# ig-normal-ver12_rev.net
KiCad netlist of a schematic drawn in EAGLE
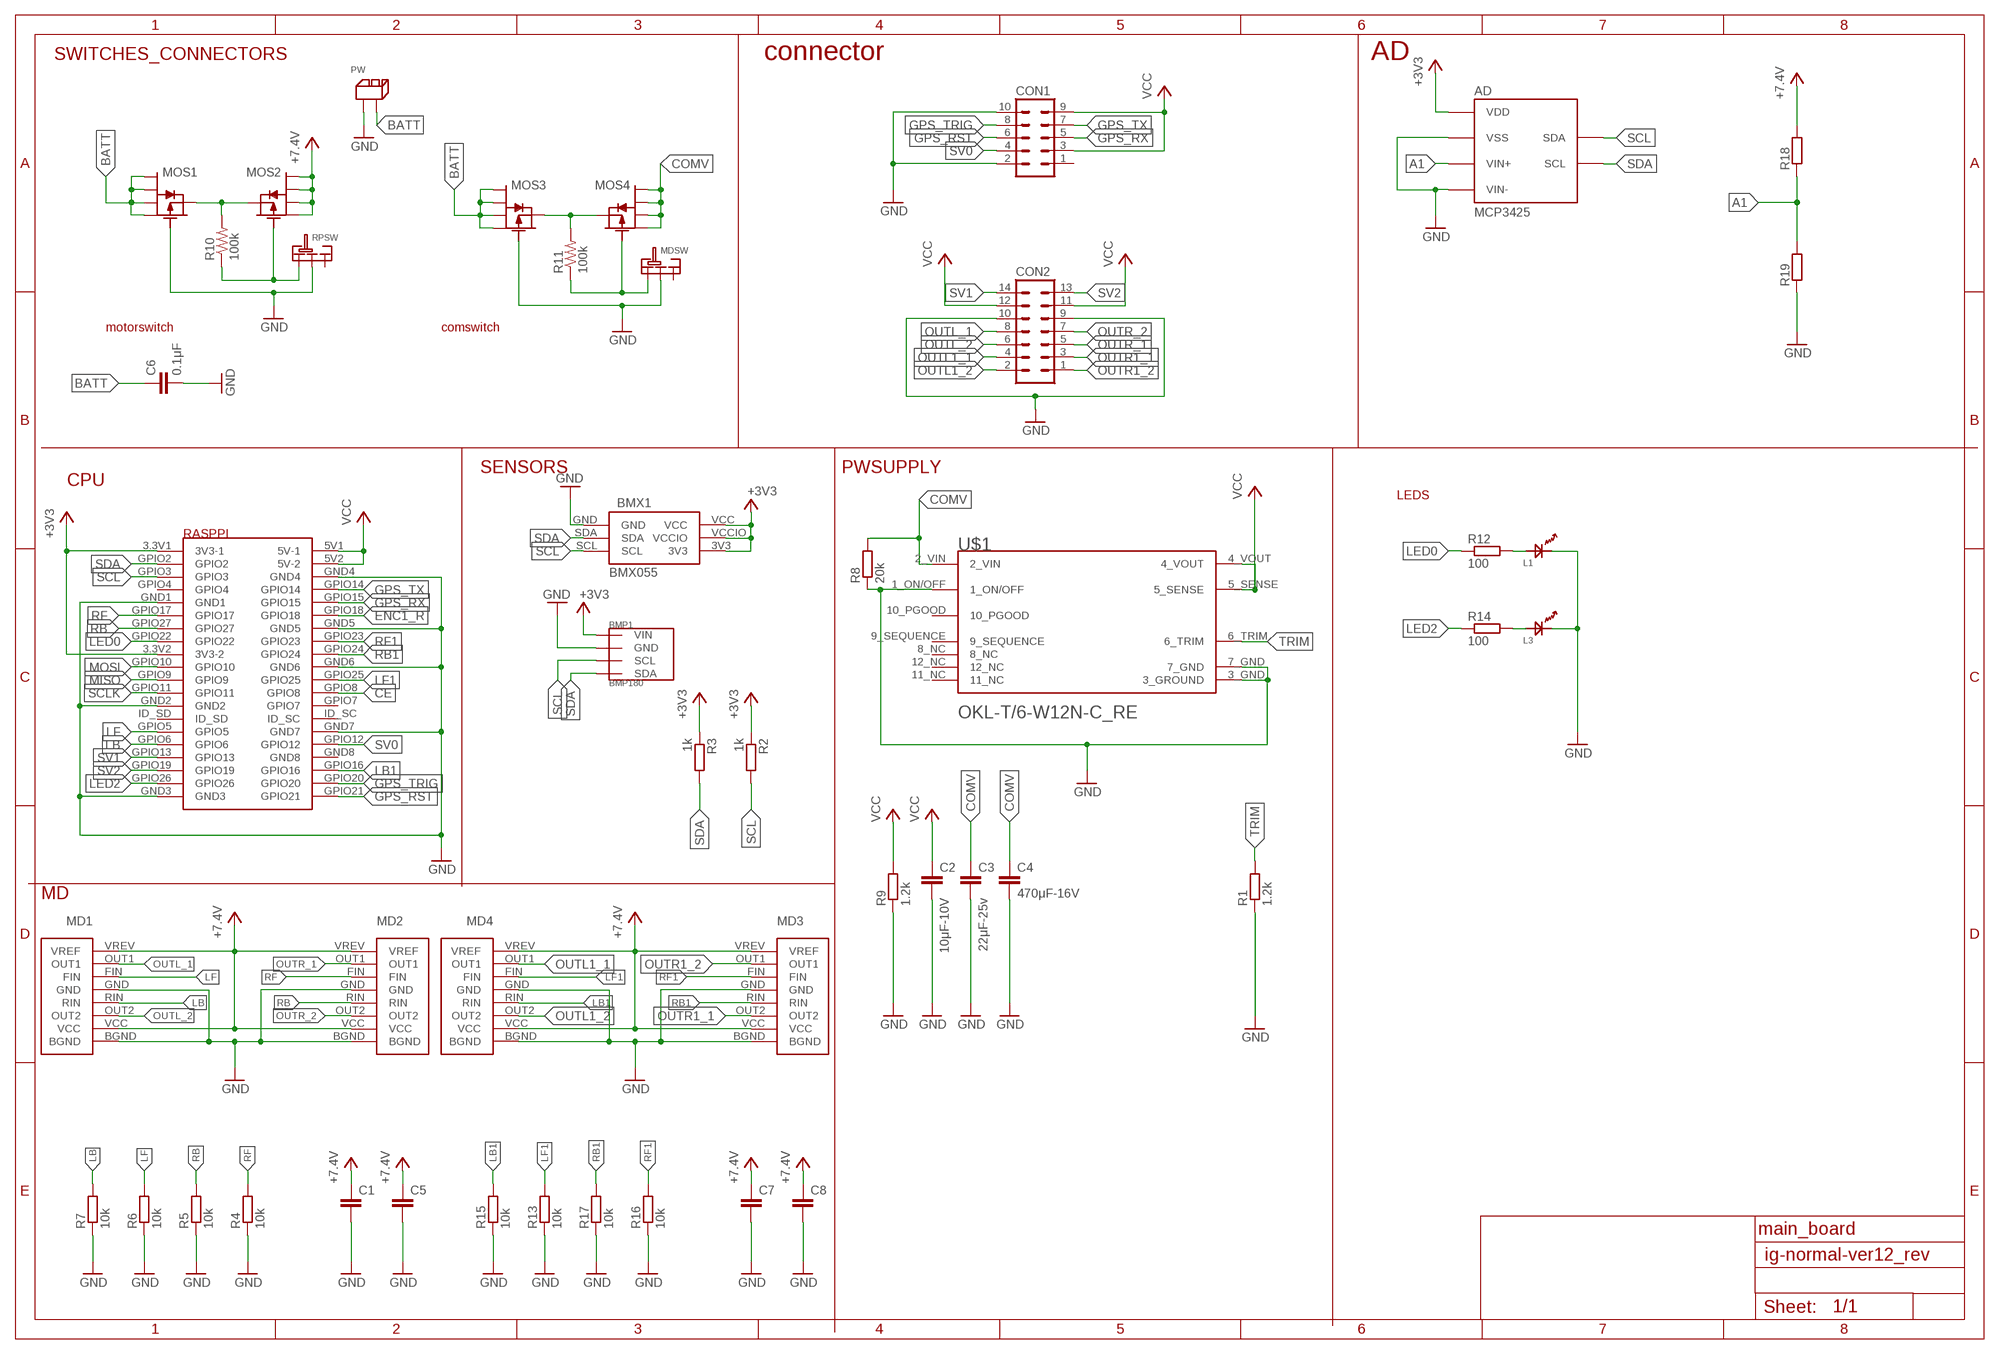
[diagram p0: schematic, sheet 1]

(export (version "E")
  (design (tool "Eeschema 10.0.6"))
  (components
    (comp (ref "AD")
      (value "MCP3425")
      (footprint "eagle-import:SOT23-6")
      (libsource (lib "eagle-import") (part "MCP3425"))
    )
    (comp (ref "BMP1")
      (value "BMP180")
      (footprint "eagle-import:GY-68")
      (libsource (lib "eagle-import") (part "BMP180"))
    )
    (comp (ref "BMX1")
      (value "BMX055")
      (footprint "eagle-import:BMX055")
      (libsource (lib "eagle-import") (part "BMX055"))
    )
    (comp (ref "C1")
      (value "C-EUC0603")
      (footprint "eagle-import:C0603")
      (libsource (lib "eagle-import") (part "C-EUC0603"))
    )
    (comp (ref "C2")
      (value "10μF-10V")
      (footprint "eagle-import:C0603")
      (libsource (lib "eagle-import") (part "C-EUC0603"))
    )
    (comp (ref "C3")
      (value "22μF-25v")
      (footprint "eagle-import:C0805")
      (libsource (lib "eagle-import") (part "C-EUC0805"))
    )
    (comp (ref "C4")
      (value "470μF-16V")
      (footprint "eagle-import:C0603")
      (libsource (lib "eagle-import") (part "C-EUC0603"))
    )
    (comp (ref "C5")
      (value "C-EUC0603")
      (footprint "eagle-import:C0603")
      (libsource (lib "eagle-import") (part "C-EUC0603"))
    )
    (comp (ref "C6")
      (value "0.1μF")
      (footprint "eagle-import:C0603")
      (libsource (lib "eagle-import") (part "C-EUC0603"))
    )
    (comp (ref "C7")
      (value "C-EUC0603")
      (footprint "eagle-import:C0603")
      (libsource (lib "eagle-import") (part "C-EUC0603"))
    )
    (comp (ref "C8")
      (value "C-EUC0603")
      (footprint "eagle-import:C0603")
      (libsource (lib "eagle-import") (part "C-EUC0603"))
    )
    (comp (ref "CON1")
      (value "ML10L")
      (footprint "eagle-import:ML10L")
      (libsource (lib "eagle-import") (part "ML10L"))
    )
    (comp (ref "CON2")
      (value "ML14L")
      (footprint "eagle-import:ML14L")
      (libsource (lib "eagle-import") (part "ML14L"))
    )
    (comp (ref "L1")
      (value "OSXX1608C1A")
      (footprint "eagle-import:OSXX1608C1A")
      (libsource (lib "eagle-import") (part "OSXX1608C1A"))
    )
    (comp (ref "L3")
      (value "OSXX1608C1A")
      (footprint "eagle-import:OSXX1608C1A")
      (libsource (lib "eagle-import") (part "OSXX1608C1A"))
    )
    (comp (ref "MD1")
      (value "BD6222HFP-TR")
      (footprint "eagle-import:BD6222HFP-TR")
      (libsource (lib "eagle-import") (part "BD6222HFP-TR"))
    )
    (comp (ref "MD2")
      (value "BD6222HFP-TR")
      (footprint "eagle-import:BD6222HFP-TR")
      (libsource (lib "eagle-import") (part "BD6222HFP-TR"))
    )
    (comp (ref "MD3")
      (value "BD6222HFP-TR")
      (footprint "eagle-import:BD6222HFP-TR")
      (libsource (lib "eagle-import") (part "BD6222HFP-TR"))
    )
    (comp (ref "MD4")
      (value "BD6222HFP-TR")
      (footprint "eagle-import:BD6222HFP-TR")
      (libsource (lib "eagle-import") (part "BD6222HFP-TR"))
    )
    (comp (ref "MDSW")
      (value "SRIDE_SWITCH")
      (footprint "eagle-import:SRIDE_SWITCH")
      (libsource (lib "eagle-import") (part "SRIDE_SWITCH"))
    )
    (comp (ref "MOS1")
      (value "PCH_SSM6J808R")
      (footprint "eagle-import:SSM6J808R")
      (libsource (lib "eagle-import") (part "PCH_SSM6J808R"))
    )
    (comp (ref "MOS2")
      (value "PCH_SSM6J808R")
      (footprint "eagle-import:SSM6J808R")
      (libsource (lib "eagle-import") (part "PCH_SSM6J808R"))
    )
    (comp (ref "MOS3")
      (value "PCH_SSM6J808R")
      (footprint "eagle-import:SSM6J808R")
      (libsource (lib "eagle-import") (part "PCH_SSM6J808R"))
    )
    (comp (ref "MOS4")
      (value "PCH_SSM6J808R")
      (footprint "eagle-import:SSM6J808R")
      (libsource (lib "eagle-import") (part "PCH_SSM6J808R"))
    )
    (comp (ref "PW")
      (value "2PIN")
      (footprint "eagle-import:2PIN")
      (libsource (lib "eagle-import") (part "2PIN"))
    )
    (comp (ref "R1")
      (value "1.2k")
      (footprint "eagle-import:R0805")
      (libsource (lib "eagle-import") (part "R-EU_R0805"))
    )
    (comp (ref "R2")
      (value "1k")
      (footprint "eagle-import:R0603")
      (libsource (lib "eagle-import") (part "R-EU_R0603"))
    )
    (comp (ref "R3")
      (value "1k")
      (footprint "eagle-import:R0603")
      (libsource (lib "eagle-import") (part "R-EU_R0603"))
    )
    (comp (ref "R4")
      (value "10k")
      (footprint "eagle-import:R0603")
      (libsource (lib "eagle-import") (part "R-EU_R0603"))
    )
    (comp (ref "R5")
      (value "10k")
      (footprint "eagle-import:R0603")
      (libsource (lib "eagle-import") (part "R-EU_R0603"))
    )
    (comp (ref "R6")
      (value "10k")
      (footprint "eagle-import:R0603")
      (libsource (lib "eagle-import") (part "R-EU_R0603"))
    )
    (comp (ref "R7")
      (value "10k")
      (footprint "eagle-import:R0603")
      (libsource (lib "eagle-import") (part "R-EU_R0603"))
    )
    (comp (ref "R8")
      (value "20k")
      (footprint "eagle-import:R0603")
      (libsource (lib "eagle-import") (part "R-EU_R0603"))
    )
    (comp (ref "R9")
      (value "1.2k")
      (footprint "eagle-import:R0805")
      (libsource (lib "eagle-import") (part "R-EU_R0805"))
    )
    (comp (ref "R10")
      (value "100k")
      (footprint "eagle-import:R0603")
      (libsource (lib "eagle-import") (part "R-US_R0603"))
    )
    (comp (ref "R11")
      (value "100k")
      (footprint "eagle-import:R0603")
      (libsource (lib "eagle-import") (part "R-US_R0603"))
    )
    (comp (ref "R12")
      (value "100")
      (footprint "eagle-import:R0603")
      (libsource (lib "eagle-import") (part "R-EU_R0603"))
    )
    (comp (ref "R13")
      (value "10k")
      (footprint "eagle-import:R0603")
      (libsource (lib "eagle-import") (part "R-EU_R0603"))
    )
    (comp (ref "R14")
      (value "100")
      (footprint "eagle-import:R0603")
      (libsource (lib "eagle-import") (part "R-EU_R0603"))
    )
    (comp (ref "R15")
      (value "10k")
      (footprint "eagle-import:R0603")
      (libsource (lib "eagle-import") (part "R-EU_R0603"))
    )
    (comp (ref "R16")
      (value "10k")
      (footprint "eagle-import:R0603")
      (libsource (lib "eagle-import") (part "R-EU_R0603"))
    )
    (comp (ref "R17")
      (value "10k")
      (footprint "eagle-import:R0603")
      (libsource (lib "eagle-import") (part "R-EU_R0603"))
    )
    (comp (ref "R18")
      (value "R-EU_R0603")
      (footprint "eagle-import:R0603")
      (libsource (lib "eagle-import") (part "R-EU_R0603"))
    )
    (comp (ref "R19")
      (value "R-EU_R0603")
      (footprint "eagle-import:R0603")
      (libsource (lib "eagle-import") (part "R-EU_R0603"))
    )
    (comp (ref "RASPPI")
      (value "RASPBERYPIZEROW")
      (footprint "eagle-import:RASPBERYPIZEROW")
      (libsource (lib "eagle-import") (part "RASPBERYPIZEROW"))
    )
    (comp (ref "RPSW")
      (value "SRIDE_SWITCH")
      (footprint "eagle-import:SRIDE_SWITCH")
      (libsource (lib "eagle-import") (part "SRIDE_SWITCH"))
    )
    (comp (ref "U$1")
      (value "OKL-T/6-W12N-C_RE")
      (footprint "eagle-import:MURATA_IKL-T-6-W12N-C_0_RECOMENDED")
      (libsource (lib "eagle-import") (part "OKL-T/6-W12N-C_RE"))
    )
  )
  (nets
    (net (code "1") (name "+3V3") (class "Default")
      (node (ref "AD") (pin "5") (pinfunction "VDD_5") (pintype "power_in"))
      (node (ref "BMP1") (pin "P1") (pinfunction "VIN_P1") (pintype "bidirectional"))
      (node (ref "BMX1") (pin "3V3") (pinfunction "3V3_3V3") (pintype "power_in"))
      (node (ref "BMX1") (pin "VCC") (pinfunction "VCC_VCC") (pintype "power_in"))
      (node (ref "BMX1") (pin "VCCIO") (pinfunction "VCCIO_VCCIO") (pintype "power_in"))
      (node (ref "R2") (pin "1") (pinfunction "1_1") (pintype "passive"))
      (node (ref "R3") (pin "1") (pinfunction "1_1") (pintype "passive"))
      (node (ref "RASPPI") (pin "3.3V1") (pinfunction "3V3-1_3.3V1") (pintype "bidirectional"))
      (node (ref "RASPPI") (pin "3.3V2") (pinfunction "3V3-2_3.3V2") (pintype "bidirectional"))
    )
    (net (code "2") (name "+7.4V") (class "Default")
      (node (ref "C1") (pin "1") (pinfunction "1_1") (pintype "passive"))
      (node (ref "C5") (pin "1") (pinfunction "1_1") (pintype "passive"))
      (node (ref "C7") (pin "1") (pinfunction "1_1") (pintype "passive"))
      (node (ref "C8") (pin "1") (pinfunction "1_1") (pintype "passive"))
      (node (ref "MD1") (pin "VCC") (pinfunction "VCC_VCC") (pintype "bidirectional"))
      (node (ref "MD1") (pin "VREV") (pinfunction "VREF_VREV") (pintype "bidirectional"))
      (node (ref "MD2") (pin "VCC") (pinfunction "VCC_VCC") (pintype "bidirectional"))
      (node (ref "MD2") (pin "VREV") (pinfunction "VREF_VREV") (pintype "bidirectional"))
      (node (ref "MD3") (pin "VCC") (pinfunction "VCC_VCC") (pintype "bidirectional"))
      (node (ref "MD3") (pin "VREV") (pinfunction "VREF_VREV") (pintype "bidirectional"))
      (node (ref "MD4") (pin "VCC") (pinfunction "VCC_VCC") (pintype "bidirectional"))
      (node (ref "MD4") (pin "VREV") (pinfunction "VREF_VREV") (pintype "bidirectional"))
      (node (ref "MOS2") (pin "1") (pinfunction "1_1") (pintype "bidirectional"))
      (node (ref "MOS2") (pin "2") (pinfunction "2_2") (pintype "bidirectional"))
      (node (ref "MOS2") (pin "5") (pinfunction "5_5") (pintype "bidirectional"))
      (node (ref "MOS2") (pin "6") (pinfunction "6_6") (pintype "bidirectional"))
      (node (ref "R18") (pin "2") (pinfunction "2_2") (pintype "passive"))
    )
    (net (code "3") (name "A1") (class "Default")
      (node (ref "AD") (pin "1") (pinfunction "VIN+_1") (pintype "input"))
      (node (ref "R18") (pin "1") (pinfunction "1_1") (pintype "passive"))
      (node (ref "R19") (pin "2") (pinfunction "2_2") (pintype "passive"))
    )
    (net (code "4") (name "BATT") (class "Default")
      (node (ref "C6") (pin "1") (pinfunction "1_1") (pintype "passive"))
      (node (ref "MOS1") (pin "1") (pinfunction "1_1") (pintype "bidirectional"))
      (node (ref "MOS1") (pin "2") (pinfunction "2_2") (pintype "bidirectional"))
      (node (ref "MOS1") (pin "5") (pinfunction "5_5") (pintype "bidirectional"))
      (node (ref "MOS1") (pin "6") (pinfunction "6_6") (pintype "bidirectional"))
      (node (ref "MOS3") (pin "1") (pinfunction "1_1") (pintype "bidirectional"))
      (node (ref "MOS3") (pin "2") (pinfunction "2_2") (pintype "bidirectional"))
      (node (ref "MOS3") (pin "5") (pinfunction "5_5") (pintype "bidirectional"))
      (node (ref "MOS3") (pin "6") (pinfunction "6_6") (pintype "bidirectional"))
      (node (ref "PW") (pin "P$2") (pinfunction "P$2_P$2") (pintype "bidirectional"))
    )
    (net (code "5") (name "CE") (class "Default")
      (node (ref "RASPPI") (pin "GPIO8") (pinfunction "GPIO8_GPIO8") (pintype "bidirectional"))
    )
    (net (code "6") (name "COMV") (class "Default")
      (node (ref "C3") (pin "1") (pinfunction "1_1") (pintype "passive"))
      (node (ref "C4") (pin "1") (pinfunction "1_1") (pintype "passive"))
      (node (ref "MOS4") (pin "1") (pinfunction "1_1") (pintype "bidirectional"))
      (node (ref "MOS4") (pin "2") (pinfunction "2_2") (pintype "bidirectional"))
      (node (ref "MOS4") (pin "5") (pinfunction "5_5") (pintype "bidirectional"))
      (node (ref "MOS4") (pin "6") (pinfunction "6_6") (pintype "bidirectional"))
      (node (ref "R8") (pin "2") (pinfunction "2_2") (pintype "passive"))
      (node (ref "U$1") (pin "2_VIN") (pinfunction "2_VIN_2_VIN") (pintype "bidirectional"))
    )
    (net (code "7") (name "ENC1_R") (class "Default")
      (node (ref "RASPPI") (pin "GPIO18") (pinfunction "GPIO18_GPIO18") (pintype "bidirectional"))
    )
    (net (code "8") (name "GND") (class "Default")
      (node (ref "AD") (pin "2") (pinfunction "VSS_2") (pintype "power_in"))
      (node (ref "AD") (pin "6") (pinfunction "VIN-_6") (pintype "input"))
      (node (ref "BMP1") (pin "P2") (pinfunction "GND_P2") (pintype "bidirectional"))
      (node (ref "BMX1") (pin "GND") (pinfunction "GND_GND") (pintype "power_in"))
      (node (ref "C1") (pin "2") (pinfunction "2_2") (pintype "passive"))
      (node (ref "C2") (pin "2") (pinfunction "2_2") (pintype "passive"))
      (node (ref "C3") (pin "2") (pinfunction "2_2") (pintype "passive"))
      (node (ref "C4") (pin "2") (pinfunction "2_2") (pintype "passive"))
      (node (ref "C5") (pin "2") (pinfunction "2_2") (pintype "passive"))
      (node (ref "C6") (pin "2") (pinfunction "2_2") (pintype "passive"))
      (node (ref "C7") (pin "2") (pinfunction "2_2") (pintype "passive"))
      (node (ref "C8") (pin "2") (pinfunction "2_2") (pintype "passive"))
      (node (ref "CON1") (pin "10") (pinfunction "10_10") (pintype "passive"))
      (node (ref "CON1") (pin "2") (pinfunction "2_2") (pintype "passive"))
      (node (ref "CON2") (pin "10") (pinfunction "10_10") (pintype "passive"))
      (node (ref "CON2") (pin "9") (pinfunction "9_9") (pintype "passive"))
      (node (ref "L1") (pin "CT") (pinfunction "CT_CT") (pintype "bidirectional"))
      (node (ref "L3") (pin "CT") (pinfunction "CT_CT") (pintype "bidirectional"))
      (node (ref "MD1") (pin "BGND") (pinfunction "BGND_BGND") (pintype "bidirectional"))
      (node (ref "MD1") (pin "GND") (pinfunction "GND_GND") (pintype "bidirectional"))
      (node (ref "MD2") (pin "BGND") (pinfunction "BGND_BGND") (pintype "bidirectional"))
      (node (ref "MD2") (pin "GND") (pinfunction "GND_GND") (pintype "bidirectional"))
      (node (ref "MD3") (pin "BGND") (pinfunction "BGND_BGND") (pintype "bidirectional"))
      (node (ref "MD3") (pin "GND") (pinfunction "GND_GND") (pintype "bidirectional"))
      (node (ref "MD4") (pin "BGND") (pinfunction "BGND_BGND") (pintype "bidirectional"))
      (node (ref "MD4") (pin "GND") (pinfunction "GND_GND") (pintype "bidirectional"))
      (node (ref "MDSW") (pin "LR") (pinfunction "LR_LR") (pintype "bidirectional"))
      (node (ref "MOS1") (pin "3") (pinfunction "3_3") (pintype "bidirectional"))
      (node (ref "MOS3") (pin "3") (pinfunction "3_3") (pintype "bidirectional"))
      (node (ref "PW") (pin "P$1") (pinfunction "P$1_P$1") (pintype "bidirectional"))
      (node (ref "R1") (pin "1") (pinfunction "1_1") (pintype "passive"))
      (node (ref "R13") (pin "1") (pinfunction "1_1") (pintype "passive"))
      (node (ref "R15") (pin "1") (pinfunction "1_1") (pintype "passive"))
      (node (ref "R16") (pin "1") (pinfunction "1_1") (pintype "passive"))
      (node (ref "R17") (pin "1") (pinfunction "1_1") (pintype "passive"))
      (node (ref "R19") (pin "1") (pinfunction "1_1") (pintype "passive"))
      (node (ref "R4") (pin "1") (pinfunction "1_1") (pintype "passive"))
      (node (ref "R5") (pin "1") (pinfunction "1_1") (pintype "passive"))
      (node (ref "R6") (pin "1") (pinfunction "1_1") (pintype "passive"))
      (node (ref "R7") (pin "1") (pinfunction "1_1") (pintype "passive"))
      (node (ref "R8") (pin "1") (pinfunction "1_1") (pintype "passive"))
      (node (ref "R9") (pin "1") (pinfunction "1_1") (pintype "passive"))
      (node (ref "RASPPI") (pin "GND1") (pinfunction "GND1_GND1") (pintype "bidirectional"))
      (node (ref "RASPPI") (pin "GND2") (pinfunction "GND2_GND2") (pintype "bidirectional"))
      (node (ref "RASPPI") (pin "GND3") (pinfunction "GND3_GND3") (pintype "bidirectional"))
      (node (ref "RASPPI") (pin "GND4") (pinfunction "GND4_GND4") (pintype "bidirectional"))
      (node (ref "RASPPI") (pin "GND5") (pinfunction "GND5_GND5") (pintype "bidirectional"))
      (node (ref "RASPPI") (pin "GND6") (pinfunction "GND6_GND6") (pintype "bidirectional"))
      (node (ref "RASPPI") (pin "GND7") (pinfunction "GND7_GND7") (pintype "bidirectional"))
      (node (ref "RPSW") (pin "LR") (pinfunction "LR_LR") (pintype "bidirectional"))
      (node (ref "U$1") (pin "1_ON/OFF") (pinfunction "1_ON/OFF_1_ON/OFF") (pintype "bidirectional"))
      (node (ref "U$1") (pin "3_GND") (pinfunction "3_GROUND_3_GND") (pintype "power_in"))
      (node (ref "U$1") (pin "7_GND") (pinfunction "7_GND_7_GND") (pintype "power_in"))
    )
    (net (code "9") (name "GPS_RST") (class "Default")
      (node (ref "CON1") (pin "6") (pinfunction "6_6") (pintype "passive"))
      (node (ref "RASPPI") (pin "GPIO21") (pinfunction "GPIO21_GPIO21") (pintype "bidirectional"))
    )
    (net (code "10") (name "GPS_RX") (class "Default")
      (node (ref "CON1") (pin "5") (pinfunction "5_5") (pintype "passive"))
      (node (ref "RASPPI") (pin "GPIO15") (pinfunction "GPIO15_GPIO15") (pintype "bidirectional"))
    )
    (net (code "11") (name "GPS_TRIG") (class "Default")
      (node (ref "CON1") (pin "8") (pinfunction "8_8") (pintype "passive"))
      (node (ref "RASPPI") (pin "GPIO20") (pinfunction "GPIO20_GPIO20") (pintype "bidirectional"))
    )
    (net (code "12") (name "GPS_TX") (class "Default")
      (node (ref "CON1") (pin "7") (pinfunction "7_7") (pintype "passive"))
      (node (ref "RASPPI") (pin "GPIO14") (pinfunction "GPIO14_GPIO14") (pintype "bidirectional"))
    )
    (net (code "13") (name "LB") (class "Default")
      (node (ref "MD1") (pin "RIN") (pinfunction "RIN_RIN") (pintype "bidirectional"))
      (node (ref "R7") (pin "2") (pinfunction "2_2") (pintype "passive"))
      (node (ref "RASPPI") (pin "GPIO6") (pinfunction "GPIO6_GPIO6") (pintype "bidirectional"))
    )
    (net (code "14") (name "LB1") (class "Default")
      (node (ref "MD4") (pin "RIN") (pinfunction "RIN_RIN") (pintype "bidirectional"))
      (node (ref "R15") (pin "2") (pinfunction "2_2") (pintype "passive"))
      (node (ref "RASPPI") (pin "GPIO16") (pinfunction "GPIO16_GPIO16") (pintype "bidirectional"))
    )
    (net (code "15") (name "LED0") (class "Default")
      (node (ref "R12") (pin "1") (pinfunction "1_1") (pintype "passive"))
      (node (ref "RASPPI") (pin "GPIO22") (pinfunction "GPIO22_GPIO22") (pintype "bidirectional"))
    )
    (net (code "16") (name "LED2") (class "Default")
      (node (ref "R14") (pin "1") (pinfunction "1_1") (pintype "passive"))
      (node (ref "RASPPI") (pin "GPIO26") (pinfunction "GPIO26_GPIO26") (pintype "bidirectional"))
    )
    (net (code "17") (name "LF") (class "Default")
      (node (ref "MD1") (pin "FIN") (pinfunction "FIN_FIN") (pintype "bidirectional"))
      (node (ref "R6") (pin "2") (pinfunction "2_2") (pintype "passive"))
      (node (ref "RASPPI") (pin "GPIO5") (pinfunction "GPIO5_GPIO5") (pintype "bidirectional"))
    )
    (net (code "18") (name "LF1") (class "Default")
      (node (ref "MD4") (pin "FIN") (pinfunction "FIN_FIN") (pintype "bidirectional"))
      (node (ref "R13") (pin "2") (pinfunction "2_2") (pintype "passive"))
      (node (ref "RASPPI") (pin "GPIO25") (pinfunction "GPIO25_GPIO25") (pintype "bidirectional"))
    )
    (net (code "19") (name "MISO") (class "Default")
      (node (ref "RASPPI") (pin "GPIO9") (pinfunction "GPIO9_GPIO9") (pintype "bidirectional"))
    )
    (net (code "20") (name "MOSI") (class "Default")
      (node (ref "RASPPI") (pin "GPIO10") (pinfunction "GPIO10_GPIO10") (pintype "bidirectional"))
    )
    (net (code "21") (name "Net-(L1-PadAN)") (class "Default")
      (node (ref "L1") (pin "AN") (pinfunction "AN_AN") (pintype "bidirectional"))
      (node (ref "R12") (pin "2") (pinfunction "2_2") (pintype "passive"))
    )
    (net (code "22") (name "Net-(L3-PadAN)") (class "Default")
      (node (ref "L3") (pin "AN") (pinfunction "AN_AN") (pintype "bidirectional"))
      (node (ref "R14") (pin "2") (pinfunction "2_2") (pintype "passive"))
    )
    (net (code "23") (name "Net-(MDSW-PadL)") (class "Default")
      (node (ref "MDSW") (pin "L") (pinfunction "L_L") (pintype "bidirectional"))
      (node (ref "MOS4") (pin "3") (pinfunction "3_3") (pintype "bidirectional"))
      (node (ref "R11") (pin "1") (pinfunction "1_1") (pintype "passive"))
    )
    (net (code "24") (name "Net-(MOS1-Pad4)") (class "Default")
      (node (ref "MOS1") (pin "4") (pinfunction "4_4") (pintype "bidirectional"))
      (node (ref "MOS2") (pin "4") (pinfunction "4_4") (pintype "bidirectional"))
      (node (ref "R10") (pin "2") (pinfunction "2_2") (pintype "passive"))
    )
    (net (code "25") (name "Net-(MOS2-Pad3)") (class "Default")
      (node (ref "MOS2") (pin "3") (pinfunction "3_3") (pintype "bidirectional"))
      (node (ref "R10") (pin "1") (pinfunction "1_1") (pintype "passive"))
      (node (ref "RPSW") (pin "L") (pinfunction "L_L") (pintype "bidirectional"))
    )
    (net (code "26") (name "Net-(MOS3-Pad4)") (class "Default")
      (node (ref "MOS3") (pin "4") (pinfunction "4_4") (pintype "bidirectional"))
      (node (ref "MOS4") (pin "4") (pinfunction "4_4") (pintype "bidirectional"))
      (node (ref "R11") (pin "2") (pinfunction "2_2") (pintype "passive"))
    )
    (net (code "27") (name "OUTL1_1") (class "Default")
      (node (ref "CON2") (pin "4") (pinfunction "4_4") (pintype "passive"))
      (node (ref "MD4") (pin "OUT1") (pinfunction "OUT1_OUT1") (pintype "bidirectional"))
    )
    (net (code "28") (name "OUTL1_2") (class "Default")
      (node (ref "CON2") (pin "2") (pinfunction "2_2") (pintype "passive"))
      (node (ref "MD4") (pin "OUT2") (pinfunction "OUT2_OUT2") (pintype "bidirectional"))
    )
    (net (code "29") (name "OUTL_1") (class "Default")
      (node (ref "CON2") (pin "8") (pinfunction "8_8") (pintype "passive"))
      (node (ref "MD1") (pin "OUT1") (pinfunction "OUT1_OUT1") (pintype "bidirectional"))
    )
    (net (code "30") (name "OUTL_2") (class "Default")
      (node (ref "CON2") (pin "6") (pinfunction "6_6") (pintype "passive"))
      (node (ref "MD1") (pin "OUT2") (pinfunction "OUT2_OUT2") (pintype "bidirectional"))
    )
    (net (code "31") (name "OUTR1_1") (class "Default")
      (node (ref "CON2") (pin "3") (pinfunction "3_3") (pintype "passive"))
      (node (ref "MD3") (pin "OUT2") (pinfunction "OUT2_OUT2") (pintype "bidirectional"))
    )
    (net (code "32") (name "OUTR1_2") (class "Default")
      (node (ref "CON2") (pin "1") (pinfunction "1_1") (pintype "passive"))
      (node (ref "MD3") (pin "OUT1") (pinfunction "OUT1_OUT1") (pintype "bidirectional"))
    )
    (net (code "33") (name "OUTR_1") (class "Default")
      (node (ref "CON2") (pin "5") (pinfunction "5_5") (pintype "passive"))
      (node (ref "MD2") (pin "OUT1") (pinfunction "OUT1_OUT1") (pintype "bidirectional"))
    )
    (net (code "34") (name "OUTR_2") (class "Default")
      (node (ref "CON2") (pin "7") (pinfunction "7_7") (pintype "passive"))
      (node (ref "MD2") (pin "OUT2") (pinfunction "OUT2_OUT2") (pintype "bidirectional"))
    )
    (net (code "35") (name "RB") (class "Default")
      (node (ref "MD2") (pin "RIN") (pinfunction "RIN_RIN") (pintype "bidirectional"))
      (node (ref "R5") (pin "2") (pinfunction "2_2") (pintype "passive"))
      (node (ref "RASPPI") (pin "GPIO27") (pinfunction "GPIO27_GPIO27") (pintype "bidirectional"))
    )
    (net (code "36") (name "RB1") (class "Default")
      (node (ref "MD3") (pin "RIN") (pinfunction "RIN_RIN") (pintype "bidirectional"))
      (node (ref "R17") (pin "2") (pinfunction "2_2") (pintype "passive"))
      (node (ref "RASPPI") (pin "GPIO24") (pinfunction "GPIO24_GPIO24") (pintype "bidirectional"))
    )
    (net (code "37") (name "RF") (class "Default")
      (node (ref "MD2") (pin "FIN") (pinfunction "FIN_FIN") (pintype "bidirectional"))
      (node (ref "R4") (pin "2") (pinfunction "2_2") (pintype "passive"))
      (node (ref "RASPPI") (pin "GPIO17") (pinfunction "GPIO17_GPIO17") (pintype "bidirectional"))
    )
    (net (code "38") (name "RF1") (class "Default")
      (node (ref "MD3") (pin "FIN") (pinfunction "FIN_FIN") (pintype "bidirectional"))
      (node (ref "R16") (pin "2") (pinfunction "2_2") (pintype "passive"))
      (node (ref "RASPPI") (pin "GPIO23") (pinfunction "GPIO23_GPIO23") (pintype "bidirectional"))
    )
    (net (code "39") (name "SCL") (class "Default")
      (node (ref "AD") (pin "4") (pinfunction "SDA_4") (pintype "bidirectional"))
      (node (ref "BMP1") (pin "P3") (pinfunction "SCL_P3") (pintype "bidirectional"))
      (node (ref "BMX1") (pin "SCL") (pinfunction "SCL_SCL") (pintype "bidirectional"))
      (node (ref "R2") (pin "2") (pinfunction "2_2") (pintype "passive"))
      (node (ref "RASPPI") (pin "GPIO3") (pinfunction "GPIO3_GPIO3") (pintype "bidirectional"))
    )
    (net (code "40") (name "SCLK") (class "Default")
      (node (ref "RASPPI") (pin "GPIO11") (pinfunction "GPIO11_GPIO11") (pintype "bidirectional"))
    )
    (net (code "41") (name "SDA") (class "Default")
      (node (ref "AD") (pin "3") (pinfunction "SCL_3") (pintype "bidirectional"))
      (node (ref "BMP1") (pin "P4") (pinfunction "SDA_P4") (pintype "bidirectional"))
      (node (ref "BMX1") (pin "SDA") (pinfunction "SDA_SDA") (pintype "bidirectional"))
      (node (ref "R3") (pin "2") (pinfunction "2_2") (pintype "passive"))
      (node (ref "RASPPI") (pin "GPIO2") (pinfunction "GPIO2_GPIO2") (pintype "bidirectional"))
    )
    (net (code "42") (name "SV0") (class "Default")
      (node (ref "CON1") (pin "4") (pinfunction "4_4") (pintype "passive"))
      (node (ref "RASPPI") (pin "GPIO12") (pinfunction "GPIO12_GPIO12") (pintype "bidirectional"))
    )
    (net (code "43") (name "SV1") (class "Default")
      (node (ref "CON2") (pin "14") (pinfunction "14_14") (pintype "passive"))
      (node (ref "RASPPI") (pin "GPIO13") (pinfunction "GPIO13_GPIO13") (pintype "bidirectional"))
    )
    (net (code "44") (name "SV2") (class "Default")
      (node (ref "CON2") (pin "13") (pinfunction "13_13") (pintype "passive"))
      (node (ref "RASPPI") (pin "GPIO19") (pinfunction "GPIO19_GPIO19") (pintype "bidirectional"))
    )
    (net (code "45") (name "TRIM") (class "Default")
      (node (ref "R1") (pin "2") (pinfunction "2_2") (pintype "passive"))
      (node (ref "U$1") (pin "6_TRIM") (pinfunction "6_TRIM_6_TRIM") (pintype "passive"))
    )
    (net (code "46") (name "VCC") (class "Default")
      (node (ref "C2") (pin "1") (pinfunction "1_1") (pintype "passive"))
      (node (ref "CON1") (pin "3") (pinfunction "3_3") (pintype "passive"))
      (node (ref "CON1") (pin "9") (pinfunction "9_9") (pintype "passive"))
      (node (ref "CON2") (pin "11") (pinfunction "11_11") (pintype "passive"))
      (node (ref "CON2") (pin "12") (pinfunction "12_12") (pintype "passive"))
      (node (ref "R9") (pin "2") (pinfunction "2_2") (pintype "passive"))
      (node (ref "RASPPI") (pin "5V1") (pinfunction "5V-1_5V1") (pintype "bidirectional"))
      (node (ref "RASPPI") (pin "5V2") (pinfunction "5V-2_5V2") (pintype "bidirectional"))
      (node (ref "U$1") (pin "4_VOUT") (pinfunction "4_VOUT_4_VOUT") (pintype "bidirectional"))
      (node (ref "U$1") (pin "5_SENSE") (pinfunction "5_SENSE_5_SENSE") (pintype "passive"))
    )
    (net (code "47") (name "unconnected-(CON1-Pad1)") (class "Default")
      (node (ref "CON1") (pin "1") (pinfunction "1_1") (pintype "passive"))
    )
    (net (code "48") (name "unconnected-(MDSW-PadR)") (class "Default")
      (node (ref "MDSW") (pin "R") (pinfunction "R_R") (pintype "bidirectional"))
    )
    (net (code "49") (name "unconnected-(RASPPI-PadGND8)") (class "Default")
      (node (ref "RASPPI") (pin "GND8") (pinfunction "GND8_GND8") (pintype "bidirectional"))
    )
    (net (code "50") (name "unconnected-(RASPPI-PadGPIO4)") (class "Default")
      (node (ref "RASPPI") (pin "GPIO4") (pinfunction "GPIO4_GPIO4") (pintype "bidirectional"))
    )
    (net (code "51") (name "unconnected-(RASPPI-PadGPIO7)") (class "Default")
      (node (ref "RASPPI") (pin "GPIO7") (pinfunction "GPIO7_GPIO7") (pintype "bidirectional"))
    )
    (net (code "52") (name "unconnected-(RASPPI-PadID_SC)") (class "Default")
      (node (ref "RASPPI") (pin "ID_SC") (pinfunction "ID_SC_ID_SC") (pintype "bidirectional"))
    )
    (net (code "53") (name "unconnected-(RASPPI-PadID_SD)") (class "Default")
      (node (ref "RASPPI") (pin "ID_SD") (pinfunction "ID_SD_ID_SD") (pintype "bidirectional"))
    )
    (net (code "54") (name "unconnected-(RPSW-PadR)") (class "Default")
      (node (ref "RPSW") (pin "R") (pinfunction "R_R") (pintype "bidirectional"))
    )
    (net (code "55") (name "unconnected-(U$1-Pad8_NC)") (class "Default")
      (node (ref "U$1") (pin "8_NC") (pinfunction "8_NC_8_NC") (pintype "passive"))
    )
    (net (code "56") (name "unconnected-(U$1-Pad9_SEQUENCE)") (class "Default")
      (node (ref "U$1") (pin "9_SEQUENCE") (pinfunction "9_SEQUENCE_9_SEQUENCE") (pintype "passive"))
    )
    (net (code "57") (name "unconnected-(U$1-Pad10_PGOOD)") (class "Default")
      (node (ref "U$1") (pin "10_PGOOD") (pinfunction "10_PGOOD_10_PGOOD") (pintype "open_collector"))
    )
    (net (code "58") (name "unconnected-(U$1-Pad11_NC)") (class "Default")
      (node (ref "U$1") (pin "11_NC") (pinfunction "11_NC_11_NC") (pintype "passive"))
    )
    (net (code "59") (name "unconnected-(U$1-Pad12_NC)") (class "Default")
      (node (ref "U$1") (pin "12_NC") (pinfunction "12_NC_12_NC") (pintype "passive"))
    )
  )
)
